# ESC_Schematic_1.net
KiCad netlist of a schematic drawn in Altium Designer
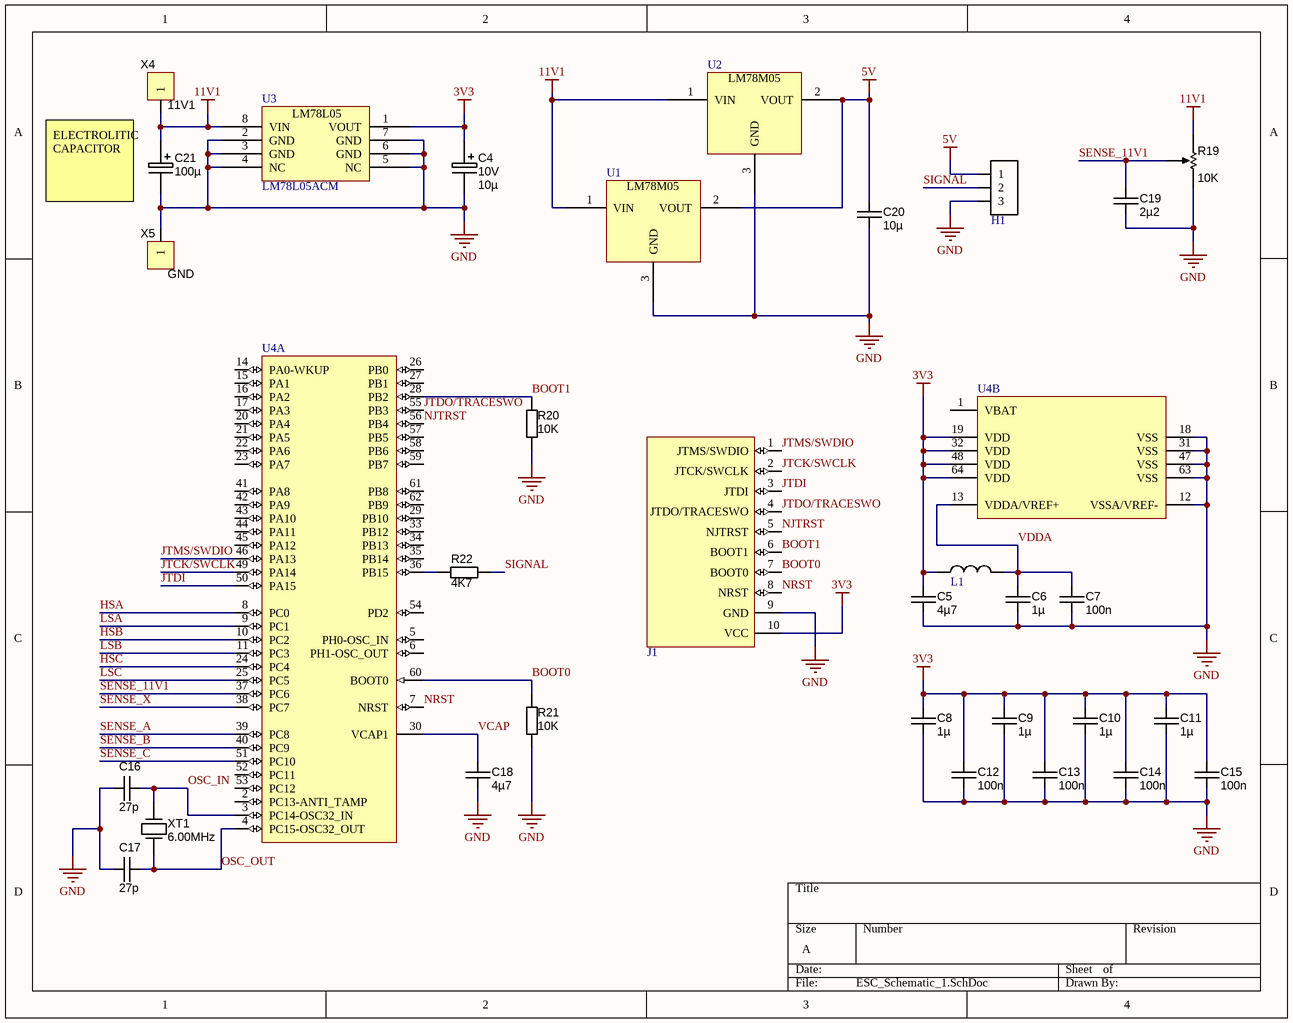
[diagram p0: ESC_Schematic_1.SchDoc]

(export (version "E")
  (design (tool "Eeschema 10.0.6"))
  (components
    (comp (ref "C4")
      (value "10µ")
      (footprint "CAPMP2012X150USR")
      (description "Capacitor SMD Tantalum 10uF 20% 10V 0805")
      (fields (field (name "TOLERANCE") "±20%") (field (name "RATINGS") "10V"))
      (libsource (lib "PBL - Capacitors") (part "CAPT_10u_0805_10V"))
    )
    (comp (ref "C5")
      (value "4µ7")
      (footprint "CAPC2012X135N")
      (description "Capacitor SMD Cer 4.7uF 10% 16V X5R 0805")
      (fields (field (name "TOLERANCE") "±10%") (field (name "Comment") "approved sub OK"))
      (libsource (lib "PBL - Capacitors") (part "CAPC_4u7_0805"))
    )
    (comp (ref "C6")
      (value "1µ")
      (footprint "CAPC2012X135N")
      (description "Capacitor SMD Cer 1uF 10% 16V X7R 0805")
      (fields (field (name "TOLERANCE") "±10%") (field (name "Comment") "approved sub OK"))
      (libsource (lib "PBL - Capacitors") (part "CAPC_1u_0805_X7R_16V_10%"))
    )
    (comp (ref "C7")
      (value "100n")
      (footprint "CAPC2012X135N")
      (description "Capacitor SMD Cer 100nF 10% 50V X7R 0805")
      (fields (field (name "TOLERANCE") "±10%") (field (name "Comment") "approved sub OK"))
      (libsource (lib "PBL - Capacitors") (part "CAPC_100n_0805_X7R_50V_10%"))
    )
    (comp (ref "C8")
      (value "1µ")
      (footprint "CAPC2012X135N")
      (description "Capacitor SMD Cer 1uF 10% 16V X7R 0805")
      (fields (field (name "TOLERANCE") "±10%") (field (name "Comment") "approved sub OK"))
      (libsource (lib "PBL - Capacitors") (part "CAPC_1u_0805_X7R_16V_10%"))
    )
    (comp (ref "C9")
      (value "1µ")
      (footprint "CAPC2012X135N")
      (description "Capacitor SMD Cer 1uF 10% 16V X7R 0805")
      (fields (field (name "TOLERANCE") "±10%") (field (name "Comment") "approved sub OK"))
      (libsource (lib "PBL - Capacitors") (part "CAPC_1u_0805_X7R_16V_10%"))
    )
    (comp (ref "C10")
      (value "1µ")
      (footprint "CAPC2012X135N")
      (description "Capacitor SMD Cer 1uF 10% 16V X7R 0805")
      (fields (field (name "TOLERANCE") "±10%") (field (name "Comment") "approved sub OK"))
      (libsource (lib "PBL - Capacitors") (part "CAPC_1u_0805_X7R_16V_10%"))
    )
    (comp (ref "C11")
      (value "1µ")
      (footprint "CAPC2012X135N")
      (description "Capacitor SMD Cer 1uF 10% 16V X7R 0805")
      (fields (field (name "TOLERANCE") "±10%") (field (name "Comment") "approved sub OK"))
      (libsource (lib "PBL - Capacitors") (part "CAPC_1u_0805_X7R_16V_10%"))
    )
    (comp (ref "C12")
      (value "100n")
      (footprint "CAPC2012X135N")
      (description "Capacitor SMD Cer 100nF 10% 50V X7R 0805")
      (fields (field (name "TOLERANCE") "±10%") (field (name "Comment") "approved sub OK"))
      (libsource (lib "PBL - Capacitors") (part "CAPC_100n_0805_X7R_50V_10%"))
    )
    (comp (ref "C13")
      (value "100n")
      (footprint "CAPC2012X135N")
      (description "Capacitor SMD Cer 100nF 10% 50V X7R 0805")
      (fields (field (name "TOLERANCE") "±10%") (field (name "Comment") "approved sub OK"))
      (libsource (lib "PBL - Capacitors") (part "CAPC_100n_0805_X7R_50V_10%"))
    )
    (comp (ref "C14")
      (value "100n")
      (footprint "CAPC2012X135N")
      (description "Capacitor SMD Cer 100nF 10% 50V X7R 0805")
      (fields (field (name "TOLERANCE") "±10%") (field (name "Comment") "approved sub OK"))
      (libsource (lib "PBL - Capacitors") (part "CAPC_100n_0805_X7R_50V_10%"))
    )
    (comp (ref "C15")
      (value "100n")
      (footprint "CAPC2012X135N")
      (description "Capacitor SMD Cer 100nF 10% 50V X7R 0805")
      (fields (field (name "TOLERANCE") "±10%") (field (name "Comment") "approved sub OK"))
      (libsource (lib "PBL - Capacitors") (part "CAPC_100n_0805_X7R_50V_10%"))
    )
    (comp (ref "C16")
      (value "27p")
      (footprint "CAPC2012X135N")
      (description "Capacitor SMD Cer 27pF 5% 50V NP0 0805")
      (fields (field (name "TOLERANCE") "±5%") (field (name "Comment") "approved sub OK"))
      (libsource (lib "PBL - Capacitors") (part "CAPC_27p_0805_NP0_50V_5%"))
    )
    (comp (ref "C17")
      (value "27p")
      (footprint "CAPC2012X135N")
      (description "Capacitor SMD Cer 27pF 5% 50V NP0 0805")
      (fields (field (name "TOLERANCE") "±5%") (field (name "Comment") "approved sub OK"))
      (libsource (lib "PBL - Capacitors") (part "CAPC_27p_0805_NP0_50V_5%"))
    )
    (comp (ref "C18")
      (value "4µ7")
      (footprint "CAPC2012X135N")
      (description "Capacitor SMD Cer 4.7uF 10% 16V X5R 0805")
      (fields (field (name "TOLERANCE") "±10%") (field (name "Comment") "approved sub OK"))
      (libsource (lib "PBL - Capacitors") (part "CAPC_4u7_0805"))
    )
    (comp (ref "C19")
      (value "2µ2")
      (footprint "CAPC2012X135N")
      (description "Capacitor SMD Cer 2.2uF 10% 16V X7R 0805")
      (fields (field (name "TOLERANCE") "±10%") (field (name "Comment") "approved sub OK"))
      (libsource (lib "PBL - Capacitors") (part "CAPC_2u2_0805"))
    )
    (comp (ref "C20")
      (value "10µ")
      (footprint "CAPC2012X135N")
      (description "Capacitor SMD Cer 10uF 10% 16V X7R 0805")
      (fields (field (name "TOLERANCE") "±10%") (field (name "Comment") "approved sub OK"))
      (libsource (lib "PBL - Capacitors") (part "CAPC_10u_0805_16V"))
    )
    (comp (ref "C21")
      (value "100µ")
      (footprint "CAPAE200P550X1200_FLAT2")
      (description "Capacitor THD Electrolytic 100uF 20% 16V Radial")
      (fields (field (name "TOLERANCE") "±20%") (field (name "MANUFACTURER") "Panasonic - ECG"))
      (libsource (lib "PBL - Capacitors") (part "CAPE_100u_16V_THD"))
    )
    (comp (ref "H1")
      (value "*")
      (footprint "HDR_1x3")
      (description "Header, 2-pin")
      (libsource (lib "co2_meter_integrated_library") (part "Header3P"))
    )
    (comp (ref "J1")
      (value "*")
      (footprint "SWJ-DP connector")
      (description "10 pin Serial Wire JTAG Debug Port")
      (libsource (lib "co2_meter_integrated_library") (part "SWJ-Debug Port"))
    )
    (comp (ref "L1")
      (value "*")
      (footprint "INDUCTOR")
      (description "0603 Inductor")
      (libsource (lib "co2_meter_integrated_library") (part "Inductor"))
    )
    (comp (ref "R19")
      (value "10K")
      (footprint "TrimPot_SMD_Bourns_3214G")
      (description "Trimmer SMD 10K 250mW 5-turn Side-adjust")
      (fields (field (name "TOLERANCE") "10%") (field (name "Comment") "5 Turn"))
      (libsource (lib "PBL - Resistors") (part "RES_TRIMMER_10K_5T_SMD"))
    )
    (comp (ref "R20")
      (value "10K")
      (footprint "RESC2012X70N")
      (description "Resistor SMD chip 10k Ohm 0.125W 5% 0805")
      (fields (field (name "TOLERANCE") "±5%") (field (name "Comment") "Thick Film"))
      (libsource (lib "PBL - Resistors") (part "RES_10K_0805_5%"))
    )
    (comp (ref "R21")
      (value "10K")
      (footprint "RESC2012X70N")
      (description "Resistor SMD chip 10k Ohm 0.125W 5% 0805")
      (fields (field (name "TOLERANCE") "±5%") (field (name "Comment") "Thick Film"))
      (libsource (lib "PBL - Resistors") (part "RES_10K_0805_5%"))
    )
    (comp (ref "R22")
      (value "4K7")
      (footprint "RESC2012X70N")
      (description "Resistor SMD chip 4.7k Ohm 0.125W 5% 0805")
      (fields (field (name "TOLERANCE") "±5%") (field (name "Comment") "Thick Film"))
      (libsource (lib "PBL - Resistors") (part "RES_4K7_0805_5%"))
    )
    (comp (ref "U1")
      (value "*")
      (footprint "TO-252")
      (description "LM78L05")
      (libsource (lib "co2_meter_integrated_library") (part "LM78M05CDT"))
    )
    (comp (ref "U2")
      (value "*")
      (footprint "TO-252")
      (description "LM78L05")
      (libsource (lib "co2_meter_integrated_library") (part "LM78M05CDT"))
    )
    (comp (ref "U3")
      (value "LM78L05ACM")
      (footprint "SOIC_8")
      (description "100-mA Fixed Output Linear Regulator")
      (libsource (lib "co2_meter_integrated_library") (part "LM78L05ACM"))
    )
    (comp (ref "U4")
      (value "~")
      (footprint "STM-LQFP64_N")
      (fields (field (name "MANUFACTURER") "STMicroelectronics") (field (name "PARTNUMBER") "STM32F401RBT6"))
      (libsource (lib "STMicroelectronics STM32 F4") (part "STM32F401RBT6"))
    )
    (comp (ref "X4") (value "11V1") (footprint "THP_D38_T75_B125") (libsource (lib "") (part "Term1_1")))
    (comp (ref "X5")
      (value "GND")
      (footprint "THP_D38_T75_B125")
      (libsource (lib "PBL - Pads and Jumpers") (part "Term1"))
    )
    (comp (ref "XT1")
      (value "6.00MHz")
      (footprint "CRYSTAL_HC49-US-SM")
      (description "Resonator Ceramic 6.00 MHz 30ppm")
      (libsource (lib "PBL - Resonators") (part "Crystal_6MHz_HC49/US"))
    )
  )
  (nets
    (net (code "1") (name "/BOOT0") (class "Default")
      (node (ref "J1") (pin "7") (pinfunction "BOOT0_7") (pintype "bidirectional"))
      (node (ref "R21") (pin "1") (pinfunction "1_1") (pintype "passive"))
      (node (ref "U4") (pin "60") (pinfunction "BOOT0_60") (pintype "input"))
    )
    (net (code "2") (name "/BOOT1") (class "Default")
      (node (ref "J1") (pin "6") (pinfunction "BOOT1_6") (pintype "bidirectional"))
      (node (ref "R20") (pin "1") (pinfunction "1_1") (pintype "passive"))
      (node (ref "U4") (pin "28") (pinfunction "PB2_28") (pintype "bidirectional"))
    )
    (net (code "3") (name "/HSA") (class "Default")
      (node (ref "U4") (pin "8") (pinfunction "PC0_8") (pintype "bidirectional"))
    )
    (net (code "4") (name "/HSB") (class "Default")
      (node (ref "U4") (pin "10") (pinfunction "PC2_10") (pintype "bidirectional"))
    )
    (net (code "5") (name "/HSC") (class "Default")
      (node (ref "U4") (pin "24") (pinfunction "PC4_24") (pintype "bidirectional"))
    )
    (net (code "6") (name "/JTCK{slash}SWCLK") (class "Default")
      (node (ref "J1") (pin "2") (pinfunction "JTCK/SWCLK_2") (pintype "bidirectional"))
      (node (ref "U4") (pin "49") (pinfunction "PA14_49") (pintype "bidirectional"))
    )
    (net (code "7") (name "/JTDI") (class "Default")
      (node (ref "J1") (pin "3") (pinfunction "JTDI_3") (pintype "bidirectional"))
      (node (ref "U4") (pin "50") (pinfunction "PA15_50") (pintype "bidirectional"))
    )
    (net (code "8") (name "/JTDO{slash}TRACESWO") (class "Default")
      (node (ref "J1") (pin "4") (pinfunction "JTDO/TRACESWO_4") (pintype "bidirectional"))
      (node (ref "U4") (pin "55") (pinfunction "PB3_55") (pintype "bidirectional"))
    )
    (net (code "9") (name "/JTMS{slash}SWDIO") (class "Default")
      (node (ref "J1") (pin "1") (pinfunction "JTMS/SWDIO_1") (pintype "bidirectional"))
      (node (ref "U4") (pin "46") (pinfunction "PA13_46") (pintype "bidirectional"))
    )
    (net (code "10") (name "/LSA") (class "Default")
      (node (ref "U4") (pin "9") (pinfunction "PC1_9") (pintype "bidirectional"))
    )
    (net (code "11") (name "/LSB") (class "Default")
      (node (ref "U4") (pin "11") (pinfunction "PC3_11") (pintype "bidirectional"))
    )
    (net (code "12") (name "/LSC") (class "Default")
      (node (ref "U4") (pin "25") (pinfunction "PC5_25") (pintype "bidirectional"))
    )
    (net (code "13") (name "/NJTRST") (class "Default")
      (node (ref "J1") (pin "5") (pinfunction "NJTRST_5") (pintype "bidirectional"))
      (node (ref "U4") (pin "56") (pinfunction "PB4_56") (pintype "bidirectional"))
    )
    (net (code "14") (name "/NRST") (class "Default")
      (node (ref "J1") (pin "8") (pinfunction "NRST_8") (pintype "bidirectional"))
      (node (ref "U4") (pin "7") (pinfunction "NRST_7") (pintype "bidirectional"))
    )
    (net (code "15") (name "/OSC_IN") (class "Default")
      (node (ref "C16") (pin "2") (pintype "passive"))
      (node (ref "U4") (pin "3") (pinfunction "PC14-OSC32_IN_3") (pintype "bidirectional"))
      (node (ref "XT1") (pin "2") (pinfunction "OUT_2") (pintype "passive"))
    )
    (net (code "16") (name "/OSC_OUT") (class "Default")
      (node (ref "C17") (pin "2") (pintype "passive"))
      (node (ref "U4") (pin "4") (pinfunction "PC15-OSC32_OUT_4") (pintype "bidirectional"))
      (node (ref "XT1") (pin "1") (pinfunction "IN_1") (pintype "passive"))
    )
    (net (code "17") (name "/SENSE_11V1") (class "Default")
      (node (ref "C19") (pin "1") (pintype "passive"))
      (node (ref "R19") (pin "2") (pinfunction "WIPER_2") (pintype "passive"))
      (node (ref "U4") (pin "37") (pinfunction "PC6_37") (pintype "bidirectional"))
    )
    (net (code "18") (name "/SENSE_A") (class "Default")
      (node (ref "U4") (pin "39") (pinfunction "PC8_39") (pintype "bidirectional"))
    )
    (net (code "19") (name "/SENSE_B") (class "Default")
      (node (ref "U4") (pin "40") (pinfunction "PC9_40") (pintype "bidirectional"))
    )
    (net (code "20") (name "/SENSE_C") (class "Default")
      (node (ref "U4") (pin "51") (pinfunction "PC10_51") (pintype "bidirectional"))
    )
    (net (code "21") (name "/SENSE_X") (class "Default")
      (node (ref "U4") (pin "38") (pinfunction "PC7_38") (pintype "bidirectional"))
    )
    (net (code "22") (name "/SIGNAL") (class "Default")
      (node (ref "H1") (pin "2") (pinfunction "2_2") (pintype "passive"))
      (node (ref "R22") (pin "2") (pinfunction "2_2") (pintype "passive"))
    )
    (net (code "23") (name "/VCAP") (class "Default")
      (node (ref "C18") (pin "1") (pintype "passive"))
      (node (ref "U4") (pin "30") (pinfunction "VCAP1_30") (pintype "power_in"))
    )
    (net (code "24") (name "/VDDA") (class "Default")
      (node (ref "C6") (pin "1") (pintype "passive"))
      (node (ref "C7") (pin "1") (pintype "passive"))
      (node (ref "L1") (pin "2") (pinfunction "2_2") (pintype "passive"))
      (node (ref "U4") (pin "13") (pinfunction "VDDA/VREF+_13") (pintype "power_in"))
    )
    (net (code "25") (name "3V3") (class "Default")
      (node (ref "C10") (pin "1") (pintype "passive"))
      (node (ref "C11") (pin "1") (pintype "passive"))
      (node (ref "C12") (pin "1") (pintype "passive"))
      (node (ref "C13") (pin "1") (pintype "passive"))
      (node (ref "C14") (pin "1") (pintype "passive"))
      (node (ref "C15") (pin "1") (pintype "passive"))
      (node (ref "C4") (pin "1") (pintype "passive"))
      (node (ref "C5") (pin "1") (pintype "passive"))
      (node (ref "C8") (pin "1") (pintype "passive"))
      (node (ref "C9") (pin "1") (pintype "passive"))
      (node (ref "J1") (pin "10") (pinfunction "VCC_10") (pintype "power_in"))
      (node (ref "L1") (pin "1") (pinfunction "1_1") (pintype "passive"))
      (node (ref "U3") (pin "1") (pinfunction "VOUT_1") (pintype "power_in"))
      (node (ref "U4") (pin "19") (pinfunction "VDD_19") (pintype "power_in"))
      (node (ref "U4") (pin "32") (pinfunction "VDD_32") (pintype "power_in"))
      (node (ref "U4") (pin "48") (pinfunction "VDD_48") (pintype "power_in"))
      (node (ref "U4") (pin "64") (pinfunction "VDD_64") (pintype "power_in"))
    )
    (net (code "26") (name "5V") (class "Default")
      (node (ref "C20") (pin "1") (pintype "passive"))
      (node (ref "H1") (pin "1") (pinfunction "1_1") (pintype "passive"))
      (node (ref "U1") (pin "2") (pinfunction "VOUT_2") (pintype "power_in"))
      (node (ref "U2") (pin "2") (pinfunction "VOUT_2") (pintype "power_in"))
    )
    (net (code "27") (name "11V1") (class "Default")
      (node (ref "C21") (pin "1") (pintype "passive"))
      (node (ref "R19") (pin "1") (pinfunction "CCW_1") (pintype "passive"))
      (node (ref "U1") (pin "1") (pinfunction "VIN_1") (pintype "power_in"))
      (node (ref "U2") (pin "1") (pinfunction "VIN_1") (pintype "power_in"))
      (node (ref "U3") (pin "8") (pinfunction "VIN_8") (pintype "power_in"))
      (node (ref "X4") (pin "1") (pinfunction "1_1") (pintype "passive"))
    )
    (net (code "28") (name "GND") (class "Default")
      (node (ref "C10") (pin "2") (pintype "passive"))
      (node (ref "C11") (pin "2") (pintype "passive"))
      (node (ref "C12") (pin "2") (pintype "passive"))
      (node (ref "C13") (pin "2") (pintype "passive"))
      (node (ref "C14") (pin "2") (pintype "passive"))
      (node (ref "C15") (pin "2") (pintype "passive"))
      (node (ref "C16") (pin "1") (pintype "passive"))
      (node (ref "C17") (pin "1") (pintype "passive"))
      (node (ref "C18") (pin "2") (pintype "passive"))
      (node (ref "C19") (pin "2") (pintype "passive"))
      (node (ref "C20") (pin "2") (pintype "passive"))
      (node (ref "C21") (pin "2") (pintype "passive"))
      (node (ref "C4") (pin "2") (pintype "passive"))
      (node (ref "C5") (pin "2") (pintype "passive"))
      (node (ref "C6") (pin "2") (pintype "passive"))
      (node (ref "C7") (pin "2") (pintype "passive"))
      (node (ref "C8") (pin "2") (pintype "passive"))
      (node (ref "C9") (pin "2") (pintype "passive"))
      (node (ref "H1") (pin "3") (pinfunction "3_3") (pintype "passive"))
      (node (ref "J1") (pin "9") (pinfunction "GND_9") (pintype "power_in"))
      (node (ref "R19") (pin "3") (pinfunction "CW_3") (pintype "passive"))
      (node (ref "R20") (pin "2") (pinfunction "2_2") (pintype "passive"))
      (node (ref "R21") (pin "2") (pinfunction "2_2") (pintype "passive"))
      (node (ref "U1") (pin "3") (pinfunction "GND_3") (pintype "power_in"))
      (node (ref "U2") (pin "3") (pinfunction "GND_3") (pintype "power_in"))
      (node (ref "U3") (pin "2") (pinfunction "GND_2") (pintype "power_in"))
      (node (ref "U3") (pin "3") (pinfunction "GND_3") (pintype "power_in"))
      (node (ref "U3") (pin "4") (pinfunction "NC_4") (pintype "passive"))
      (node (ref "U3") (pin "5") (pinfunction "NC_5") (pintype "passive"))
      (node (ref "U3") (pin "6") (pinfunction "GND_6") (pintype "power_in"))
      (node (ref "U3") (pin "7") (pinfunction "GND_7") (pintype "power_in"))
      (node (ref "U4") (pin "12") (pinfunction "VSSA/VREF-_12") (pintype "power_in"))
      (node (ref "U4") (pin "18") (pinfunction "VSS_18") (pintype "power_in"))
      (node (ref "U4") (pin "31") (pinfunction "VSS_31") (pintype "power_in"))
      (node (ref "U4") (pin "47") (pinfunction "VSS_47") (pintype "power_in"))
      (node (ref "U4") (pin "63") (pinfunction "VSS_63") (pintype "power_in"))
      (node (ref "X5") (pin "1") (pinfunction "1_1") (pintype "passive"))
    )
    (net (code "29") (name "Net-(U4A-PB15)") (class "Default")
      (node (ref "R22") (pin "1") (pinfunction "1_1") (pintype "passive"))
      (node (ref "U4") (pin "36") (pinfunction "PB15_36") (pintype "bidirectional"))
    )
    (net (code "30") (name "unconnected-(U4A-PA0-WKUP-Pad14)") (class "Default")
      (node (ref "U4") (pin "14") (pinfunction "PA0-WKUP_14") (pintype "bidirectional"))
    )
    (net (code "31") (name "unconnected-(U4A-PA1-Pad15)") (class "Default")
      (node (ref "U4") (pin "15") (pinfunction "PA1_15") (pintype "bidirectional"))
    )
    (net (code "32") (name "unconnected-(U4A-PA2-Pad16)") (class "Default")
      (node (ref "U4") (pin "16") (pinfunction "PA2_16") (pintype "bidirectional"))
    )
    (net (code "33") (name "unconnected-(U4A-PA3-Pad17)") (class "Default")
      (node (ref "U4") (pin "17") (pinfunction "PA3_17") (pintype "bidirectional"))
    )
    (net (code "34") (name "unconnected-(U4A-PA4-Pad20)") (class "Default")
      (node (ref "U4") (pin "20") (pinfunction "PA4_20") (pintype "bidirectional"))
    )
    (net (code "35") (name "unconnected-(U4A-PA5-Pad21)") (class "Default")
      (node (ref "U4") (pin "21") (pinfunction "PA5_21") (pintype "bidirectional"))
    )
    (net (code "36") (name "unconnected-(U4A-PA6-Pad22)") (class "Default")
      (node (ref "U4") (pin "22") (pinfunction "PA6_22") (pintype "bidirectional"))
    )
    (net (code "37") (name "unconnected-(U4A-PA7-Pad23)") (class "Default")
      (node (ref "U4") (pin "23") (pinfunction "PA7_23") (pintype "bidirectional"))
    )
    (net (code "38") (name "unconnected-(U4A-PA8-Pad41)") (class "Default")
      (node (ref "U4") (pin "41") (pinfunction "PA8_41") (pintype "bidirectional"))
    )
    (net (code "39") (name "unconnected-(U4A-PA9-Pad42)") (class "Default")
      (node (ref "U4") (pin "42") (pinfunction "PA9_42") (pintype "bidirectional"))
    )
    (net (code "40") (name "unconnected-(U4A-PA10-Pad43)") (class "Default")
      (node (ref "U4") (pin "43") (pinfunction "PA10_43") (pintype "bidirectional"))
    )
    (net (code "41") (name "unconnected-(U4A-PA11-Pad44)") (class "Default")
      (node (ref "U4") (pin "44") (pinfunction "PA11_44") (pintype "bidirectional"))
    )
    (net (code "42") (name "unconnected-(U4A-PA12-Pad45)") (class "Default")
      (node (ref "U4") (pin "45") (pinfunction "PA12_45") (pintype "bidirectional"))
    )
    (net (code "43") (name "unconnected-(U4A-PB0-Pad26)") (class "Default")
      (node (ref "U4") (pin "26") (pinfunction "PB0_26") (pintype "bidirectional"))
    )
    (net (code "44") (name "unconnected-(U4A-PB1-Pad27)") (class "Default")
      (node (ref "U4") (pin "27") (pinfunction "PB1_27") (pintype "bidirectional"))
    )
    (net (code "45") (name "unconnected-(U4A-PB5-Pad57)") (class "Default")
      (node (ref "U4") (pin "57") (pinfunction "PB5_57") (pintype "bidirectional"))
    )
    (net (code "46") (name "unconnected-(U4A-PB6-Pad58)") (class "Default")
      (node (ref "U4") (pin "58") (pinfunction "PB6_58") (pintype "bidirectional"))
    )
    (net (code "47") (name "unconnected-(U4A-PB7-Pad59)") (class "Default")
      (node (ref "U4") (pin "59") (pinfunction "PB7_59") (pintype "bidirectional"))
    )
    (net (code "48") (name "unconnected-(U4A-PB8-Pad61)") (class "Default")
      (node (ref "U4") (pin "61") (pinfunction "PB8_61") (pintype "bidirectional"))
    )
    (net (code "49") (name "unconnected-(U4A-PB9-Pad62)") (class "Default")
      (node (ref "U4") (pin "62") (pinfunction "PB9_62") (pintype "bidirectional"))
    )
    (net (code "50") (name "unconnected-(U4A-PB10-Pad29)") (class "Default")
      (node (ref "U4") (pin "29") (pinfunction "PB10_29") (pintype "bidirectional"))
    )
    (net (code "51") (name "unconnected-(U4A-PB12-Pad33)") (class "Default")
      (node (ref "U4") (pin "33") (pinfunction "PB12_33") (pintype "bidirectional"))
    )
    (net (code "52") (name "unconnected-(U4A-PB13-Pad34)") (class "Default")
      (node (ref "U4") (pin "34") (pinfunction "PB13_34") (pintype "bidirectional"))
    )
    (net (code "53") (name "unconnected-(U4A-PB14-Pad35)") (class "Default")
      (node (ref "U4") (pin "35") (pinfunction "PB14_35") (pintype "bidirectional"))
    )
    (net (code "54") (name "unconnected-(U4A-PC11-Pad52)") (class "Default")
      (node (ref "U4") (pin "52") (pinfunction "PC11_52") (pintype "bidirectional"))
    )
    (net (code "55") (name "unconnected-(U4A-PC12-Pad53)") (class "Default")
      (node (ref "U4") (pin "53") (pinfunction "PC12_53") (pintype "bidirectional"))
    )
    (net (code "56") (name "unconnected-(U4A-PC13-ANTI_TAMP-Pad2)") (class "Default")
      (node (ref "U4") (pin "2") (pinfunction "PC13-ANTI_TAMP_2") (pintype "bidirectional"))
    )
    (net (code "57") (name "unconnected-(U4A-PD2-Pad54)") (class "Default")
      (node (ref "U4") (pin "54") (pinfunction "PD2_54") (pintype "bidirectional"))
    )
    (net (code "58") (name "unconnected-(U4A-PH0-OSC_IN-Pad5)") (class "Default")
      (node (ref "U4") (pin "5") (pinfunction "PH0-OSC_IN_5") (pintype "bidirectional"))
    )
    (net (code "59") (name "unconnected-(U4A-PH1-OSC_OUT-Pad6)") (class "Default")
      (node (ref "U4") (pin "6") (pinfunction "PH1-OSC_OUT_6") (pintype "bidirectional"))
    )
    (net (code "60") (name "unconnected-(U4B-VBAT-Pad1)") (class "Default")
      (node (ref "U4") (pin "1") (pinfunction "VBAT_1") (pintype "power_in"))
    )
  )
)
